# Schematic.net
KiCad netlist of a schematic drawn in EAGLE
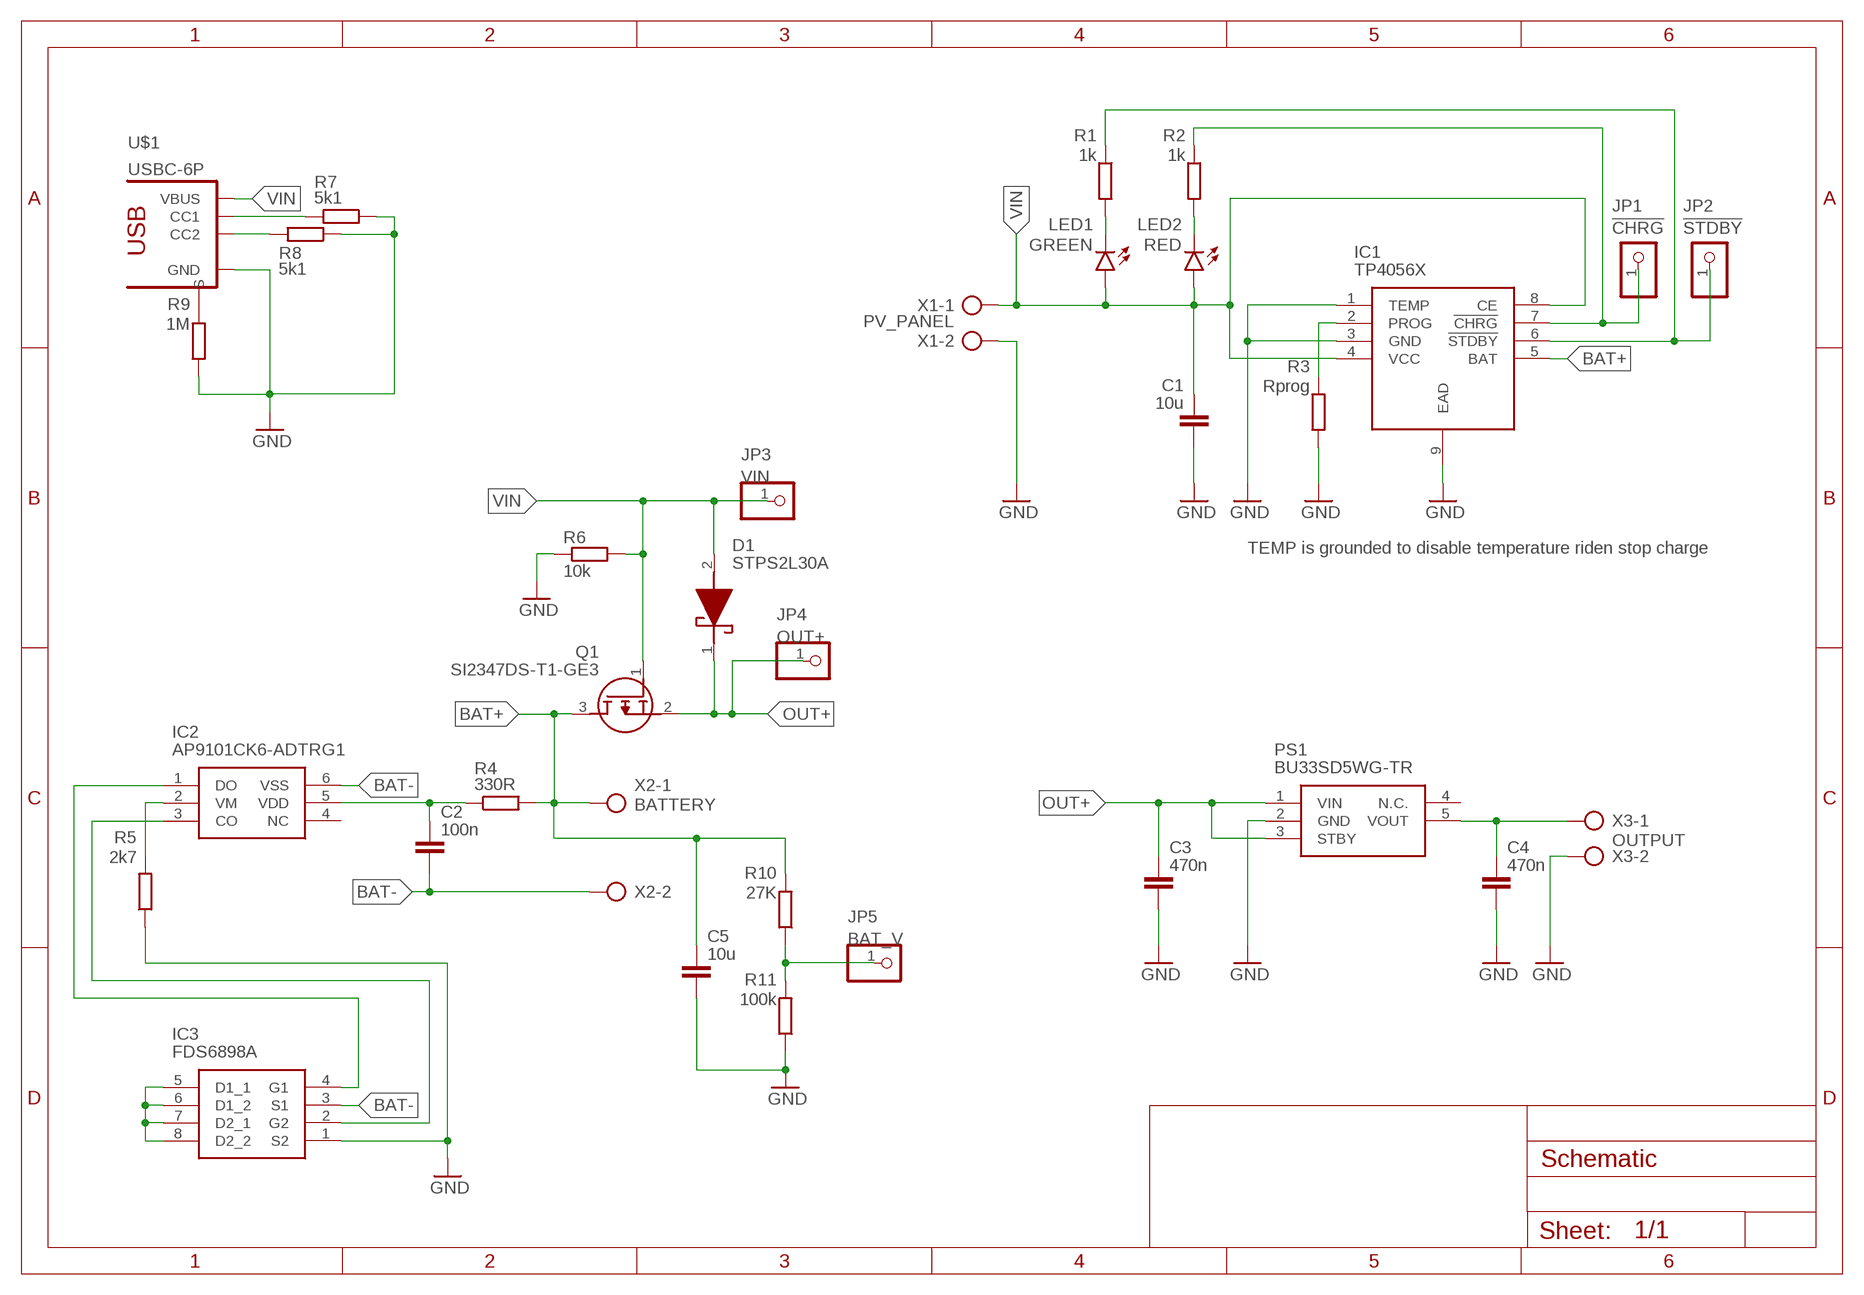
[diagram p0: schematic, sheet 1]

(export (version "E")
  (design (tool "Eeschema 10.0.6"))
  (components
    (comp (ref "C1")
      (value "10u")
      (footprint "eagle-import:C0805")
      (libsource (lib "eagle-import") (part "C-EUC0805"))
    )
    (comp (ref "C2")
      (value "100n")
      (footprint "eagle-import:C0805")
      (libsource (lib "eagle-import") (part "C-EUC0805"))
    )
    (comp (ref "C3")
      (value "470n")
      (footprint "eagle-import:C0805")
      (libsource (lib "eagle-import") (part "C-EUC0805"))
    )
    (comp (ref "C4")
      (value "470n")
      (footprint "eagle-import:C0805")
      (libsource (lib "eagle-import") (part "C-EUC0805"))
    )
    (comp (ref "C5")
      (value "10u")
      (footprint "eagle-import:C0805")
      (libsource (lib "eagle-import") (part "C-EUC0805"))
    )
    (comp (ref "D1")
      (value "STPS2L30A")
      (footprint "eagle-import:DIOM5126X265N")
      (fields (field (name "MOUSER_PART_NUMBER") "511-STPS2L30A"))
      (libsource (lib "eagle-import") (part "STPS2L30A"))
    )
    (comp (ref "IC1")
      (value "TP4056X")
      (footprint "eagle-import:SOIC127P600X175-9N")
      (libsource (lib "eagle-import") (part "TP4056X"))
    )
    (comp (ref "IC2")
      (value "AP9101CK6-ADTRG1")
      (footprint "eagle-import:SOT95P285X140-6N")
      (fields (field (name "MOUSER_PART_NUMBER") "621-AP9101CK6-ADTRG1"))
      (libsource (lib "eagle-import") (part "AP9101CK6-ADTRG1"))
    )
    (comp (ref "IC3")
      (value "FDS6898A")
      (footprint "eagle-import:SOIC127P600X175-8N")
      (fields (field (name "MOUSER_PART_NUMBER") "512-FDS6898A"))
      (libsource (lib "eagle-import") (part "FDS6898A"))
    )
    (comp (ref "JP1")
      (value "!CHRG")
      (footprint "eagle-import:1X01")
      (libsource (lib "eagle-import") (part "PINHD-1X1"))
    )
    (comp (ref "JP2")
      (value "!STDBY")
      (footprint "eagle-import:1X01")
      (libsource (lib "eagle-import") (part "PINHD-1X1"))
    )
    (comp (ref "JP3")
      (value "VIN")
      (footprint "eagle-import:1X01")
      (fields (field (name "SPICEPREFIX") "X"))
      (libsource (lib "eagle-import") (part "PINHD-1X1"))
    )
    (comp (ref "JP4")
      (value "OUT+")
      (footprint "eagle-import:1X01")
      (libsource (lib "eagle-import") (part "PINHD-1X1"))
    )
    (comp (ref "JP5")
      (value "BAT_V")
      (footprint "eagle-import:1X01")
      (libsource (lib "eagle-import") (part "PINHD-1X1"))
    )
    (comp (ref "LED1")
      (value "GREEN")
      (footprint "eagle-import:CHIPLED_0805")
      (libsource (lib "eagle-import") (part "LEDCHIPLED_0805"))
    )
    (comp (ref "LED2")
      (value "RED")
      (footprint "eagle-import:CHIPLED_0805")
      (libsource (lib "eagle-import") (part "LEDCHIPLED_0805"))
    )
    (comp (ref "PS1")
      (value "BU33SD5WG-TR")
      (footprint "eagle-import:SOT95P280X125-5N")
      (fields (field (name "MOUSER_PART_NUMBER") "755-BU33SD5WG-TR"))
      (libsource (lib "eagle-import") (part "BU33SD5WG-TR"))
    )
    (comp (ref "Q1")
      (value "SI2347DS-T1-GE3")
      (footprint "eagle-import:SOT95P237X112-3N")
      (fields
        (field (name "MANUFACTURER_PART_NUMBER") "Si2347DS-T1-GE3")
        (field (name "MOUSER_PART_NUMBER") "78-SI2347DS-T1-GE3")
      )
      (libsource (lib "eagle-import") (part "SI2347DS-T1-GE3"))
    )
    (comp (ref "R1")
      (value "1k")
      (footprint "eagle-import:R0805")
      (libsource (lib "eagle-import") (part "R-EU_R0805"))
    )
    (comp (ref "R2")
      (value "1k")
      (footprint "eagle-import:R0805")
      (libsource (lib "eagle-import") (part "R-EU_R0805"))
    )
    (comp (ref "R3")
      (value "Rprog")
      (footprint "eagle-import:R0805")
      (libsource (lib "eagle-import") (part "R-EU_R0805"))
    )
    (comp (ref "R4")
      (value "330R")
      (footprint "eagle-import:R0805")
      (libsource (lib "eagle-import") (part "R-EU_R0805"))
    )
    (comp (ref "R5")
      (value "2k7")
      (footprint "eagle-import:R0805")
      (libsource (lib "eagle-import") (part "R-EU_R0805"))
    )
    (comp (ref "R6")
      (value "10k")
      (footprint "eagle-import:R0805")
      (libsource (lib "eagle-import") (part "R-EU_R0805"))
    )
    (comp (ref "R7")
      (value "5k1")
      (footprint "eagle-import:R0805")
      (libsource (lib "eagle-import") (part "R-EU_R0805"))
    )
    (comp (ref "R8")
      (value "5k1")
      (footprint "eagle-import:R0805")
      (libsource (lib "eagle-import") (part "R-EU_R0805"))
    )
    (comp (ref "R9")
      (value "1M")
      (footprint "eagle-import:R0805")
      (libsource (lib "eagle-import") (part "R-EU_R0805"))
    )
    (comp (ref "R10")
      (value "27K")
      (footprint "eagle-import:R0805")
      (libsource (lib "eagle-import") (part "R-EU_R0805"))
    )
    (comp (ref "R11")
      (value "100k")
      (footprint "eagle-import:R0805")
      (libsource (lib "eagle-import") (part "R-EU_R0805"))
    )
    (comp (ref "U$1")
      (value "USBC-6P")
      (footprint "eagle-import:USCX-06FX-XXMX-01")
      (libsource (lib "eagle-import") (part "USBC-6P"))
    )
    (comp (ref "X1")
      (value "PV_PANEL")
      (footprint "eagle-import:AK300_2")
      (libsource (lib "eagle-import") (part "AK300/2"))
    )
    (comp (ref "X2")
      (value "BATTERY")
      (footprint "eagle-import:AK300_2")
      (libsource (lib "eagle-import") (part "AK300/2"))
    )
    (comp (ref "X3")
      (value "OUTPUT")
      (footprint "eagle-import:AK300_2")
      (libsource (lib "eagle-import") (part "AK300/2"))
    )
  )
  (nets
    (net (code "1") (name "BAT+") (class "Default")
      (node (ref "C5") (pin "1") (pinfunction "1_1") (pintype "passive"))
      (node (ref "IC1") (pin "5") (pinfunction "BAT_5") (pintype "bidirectional"))
      (node (ref "Q1") (pin "3") (pinfunction "D_3") (pintype "bidirectional"))
      (node (ref "R10") (pin "2") (pinfunction "2_2") (pintype "passive"))
      (node (ref "R4") (pin "2") (pinfunction "2_2") (pintype "passive"))
      (node (ref "X2") (pin "1") (pinfunction "KL_1") (pintype "passive"))
    )
    (net (code "2") (name "BAT-") (class "Default")
      (node (ref "C2") (pin "2") (pinfunction "2_2") (pintype "passive"))
      (node (ref "IC2") (pin "6") (pinfunction "VSS_6") (pintype "bidirectional"))
      (node (ref "IC3") (pin "3") (pinfunction "S1_3") (pintype "bidirectional"))
      (node (ref "X2") (pin "2") (pinfunction "KL_2") (pintype "passive"))
    )
    (net (code "3") (name "GND") (class "Default")
      (node (ref "C1") (pin "2") (pinfunction "2_2") (pintype "passive"))
      (node (ref "C3") (pin "2") (pinfunction "2_2") (pintype "passive"))
      (node (ref "C4") (pin "2") (pinfunction "2_2") (pintype "passive"))
      (node (ref "C5") (pin "2") (pinfunction "2_2") (pintype "passive"))
      (node (ref "IC1") (pin "1") (pinfunction "TEMP_1") (pintype "bidirectional"))
      (node (ref "IC1") (pin "3") (pinfunction "GND_3") (pintype "bidirectional"))
      (node (ref "IC1") (pin "9") (pinfunction "EAD_9") (pintype "bidirectional"))
      (node (ref "IC3") (pin "1") (pinfunction "S2_1") (pintype "bidirectional"))
      (node (ref "PS1") (pin "2") (pinfunction "GND_2") (pintype "bidirectional"))
      (node (ref "R11") (pin "1") (pinfunction "1_1") (pintype "passive"))
      (node (ref "R3") (pin "2") (pinfunction "2_2") (pintype "passive"))
      (node (ref "R5") (pin "1") (pinfunction "1_1") (pintype "passive"))
      (node (ref "R6") (pin "1") (pinfunction "1_1") (pintype "passive"))
      (node (ref "R7") (pin "1") (pinfunction "1_1") (pintype "passive"))
      (node (ref "R8") (pin "1") (pinfunction "1_1") (pintype "passive"))
      (node (ref "R9") (pin "2") (pinfunction "2_2") (pintype "passive"))
      (node (ref "U$1") (pin "GND1") (pinfunction "GND_GND1") (pintype "power_in"))
      (node (ref "U$1") (pin "GND2") (pinfunction "GND_GND2") (pintype "power_in"))
      (node (ref "X1") (pin "2") (pinfunction "KL_2") (pintype "passive"))
      (node (ref "X3") (pin "2") (pinfunction "KL_2") (pintype "passive"))
    )
    (net (code "4") (name "Net-(IC1-PROG)") (class "Default")
      (node (ref "IC1") (pin "2") (pinfunction "PROG_2") (pintype "bidirectional"))
      (node (ref "R3") (pin "1") (pinfunction "1_1") (pintype "passive"))
    )
    (net (code "5") (name "Net-(IC1-~{CHRG})") (class "Default")
      (node (ref "IC1") (pin "7") (pinfunction "~{CHRG}_7") (pintype "bidirectional"))
      (node (ref "JP1") (pin "1") (pinfunction "1_1") (pintype "passive"))
      (node (ref "R2") (pin "1") (pinfunction "1_1") (pintype "passive"))
    )
    (net (code "6") (name "Net-(IC1-~{STDBY})") (class "Default")
      (node (ref "IC1") (pin "6") (pinfunction "~{STDBY}_6") (pintype "bidirectional"))
      (node (ref "JP2") (pin "1") (pinfunction "1_1") (pintype "passive"))
      (node (ref "R1") (pin "1") (pinfunction "1_1") (pintype "passive"))
    )
    (net (code "7") (name "Net-(IC2-CO)") (class "Default")
      (node (ref "IC2") (pin "3") (pinfunction "CO_3") (pintype "bidirectional"))
      (node (ref "IC3") (pin "2") (pinfunction "G2_2") (pintype "bidirectional"))
    )
    (net (code "8") (name "Net-(IC2-DO)") (class "Default")
      (node (ref "IC2") (pin "1") (pinfunction "DO_1") (pintype "bidirectional"))
      (node (ref "IC3") (pin "4") (pinfunction "G1_4") (pintype "bidirectional"))
    )
    (net (code "9") (name "Net-(IC2-VDD)") (class "Default")
      (node (ref "C2") (pin "1") (pinfunction "1_1") (pintype "passive"))
      (node (ref "IC2") (pin "5") (pinfunction "VDD_5") (pintype "bidirectional"))
      (node (ref "R4") (pin "1") (pinfunction "1_1") (pintype "passive"))
    )
    (net (code "10") (name "Net-(IC2-VM)") (class "Default")
      (node (ref "IC2") (pin "2") (pinfunction "VM_2") (pintype "bidirectional"))
      (node (ref "R5") (pin "2") (pinfunction "2_2") (pintype "passive"))
    )
    (net (code "11") (name "Net-(IC3-D1_1)") (class "Default")
      (node (ref "IC3") (pin "5") (pinfunction "D1_1_5") (pintype "bidirectional"))
      (node (ref "IC3") (pin "6") (pinfunction "D1_2_6") (pintype "bidirectional"))
      (node (ref "IC3") (pin "7") (pinfunction "D2_1_7") (pintype "bidirectional"))
      (node (ref "IC3") (pin "8") (pinfunction "D2_2_8") (pintype "bidirectional"))
    )
    (net (code "12") (name "Net-(JP5-Pad1)") (class "Default")
      (node (ref "JP5") (pin "1") (pinfunction "1_1") (pintype "passive"))
      (node (ref "R10") (pin "1") (pinfunction "1_1") (pintype "passive"))
      (node (ref "R11") (pin "2") (pinfunction "2_2") (pintype "passive"))
    )
    (net (code "13") (name "Net-(LED1-PadC)") (class "Default")
      (node (ref "LED1") (pin "C") (pinfunction "C_C") (pintype "passive"))
      (node (ref "R1") (pin "2") (pinfunction "2_2") (pintype "passive"))
    )
    (net (code "14") (name "Net-(LED2-PadC)") (class "Default")
      (node (ref "LED2") (pin "C") (pinfunction "C_C") (pintype "passive"))
      (node (ref "R2") (pin "2") (pinfunction "2_2") (pintype "passive"))
    )
    (net (code "15") (name "Net-(PS1-VOUT)") (class "Default")
      (node (ref "C4") (pin "1") (pinfunction "1_1") (pintype "passive"))
      (node (ref "PS1") (pin "5") (pinfunction "VOUT_5") (pintype "bidirectional"))
      (node (ref "X3") (pin "1") (pinfunction "KL_1") (pintype "passive"))
    )
    (net (code "16") (name "Net-(R7-Pad2)") (class "Default")
      (node (ref "R7") (pin "2") (pinfunction "2_2") (pintype "passive"))
      (node (ref "U$1") (pin "CC1") (pinfunction "CC1_CC1") (pintype "bidirectional"))
    )
    (net (code "17") (name "Net-(R8-Pad2)") (class "Default")
      (node (ref "R8") (pin "2") (pinfunction "2_2") (pintype "passive"))
      (node (ref "U$1") (pin "CC2") (pinfunction "CC2_CC2") (pintype "bidirectional"))
    )
    (net (code "18") (name "Net-(R9-Pad1)") (class "Default")
      (node (ref "R9") (pin "1") (pinfunction "1_1") (pintype "passive"))
      (node (ref "U$1") (pin "SHIELD1") (pinfunction "S_SHIELD1") (pintype "passive"))
      (node (ref "U$1") (pin "SHIELD2") (pinfunction "S_SHIELD2") (pintype "passive"))
      (node (ref "U$1") (pin "SHIELD3") (pinfunction "S_SHIELD3") (pintype "passive"))
      (node (ref "U$1") (pin "SHIELD4") (pinfunction "S_SHIELD4") (pintype "passive"))
    )
    (net (code "19") (name "OUT+") (class "Default")
      (node (ref "C3") (pin "1") (pinfunction "1_1") (pintype "passive"))
      (node (ref "D1") (pin "1") (pinfunction "K_1") (pintype "bidirectional"))
      (node (ref "JP4") (pin "1") (pinfunction "1_1") (pintype "passive"))
      (node (ref "PS1") (pin "1") (pinfunction "VIN_1") (pintype "bidirectional"))
      (node (ref "PS1") (pin "3") (pinfunction "STBY_3") (pintype "bidirectional"))
      (node (ref "Q1") (pin "2") (pinfunction "S_2") (pintype "bidirectional"))
    )
    (net (code "20") (name "VIN") (class "Default")
      (node (ref "C1") (pin "1") (pinfunction "1_1") (pintype "passive"))
      (node (ref "D1") (pin "2") (pinfunction "A_2") (pintype "bidirectional"))
      (node (ref "IC1") (pin "4") (pinfunction "VCC_4") (pintype "bidirectional"))
      (node (ref "IC1") (pin "8") (pinfunction "CE_8") (pintype "bidirectional"))
      (node (ref "JP3") (pin "1") (pinfunction "1_1") (pintype "passive"))
      (node (ref "LED1") (pin "A") (pinfunction "A_A") (pintype "passive"))
      (node (ref "LED2") (pin "A") (pinfunction "A_A") (pintype "passive"))
      (node (ref "Q1") (pin "1") (pinfunction "G_1") (pintype "bidirectional"))
      (node (ref "R6") (pin "2") (pinfunction "2_2") (pintype "passive"))
      (node (ref "U$1") (pin "VBUS1") (pinfunction "VBUS_VBUS1") (pintype "power_in"))
      (node (ref "U$1") (pin "VBUS2") (pinfunction "VBUS_VBUS2") (pintype "power_in"))
      (node (ref "X1") (pin "1") (pinfunction "KL_1") (pintype "passive"))
    )
    (net (code "21") (name "unconnected-(IC2-NC-Pad4)") (class "Default")
      (node (ref "IC2") (pin "4") (pinfunction "NC_4") (pintype "no_connect"))
    )
    (net (code "22") (name "unconnected-(PS1-N.C.-Pad4)") (class "Default")
      (node (ref "PS1") (pin "4") (pinfunction "N.C._4") (pintype "no_connect"))
    )
  )
)
